# 20_ADC.net
KiCad netlist of a schematic drawn in Altium Designer
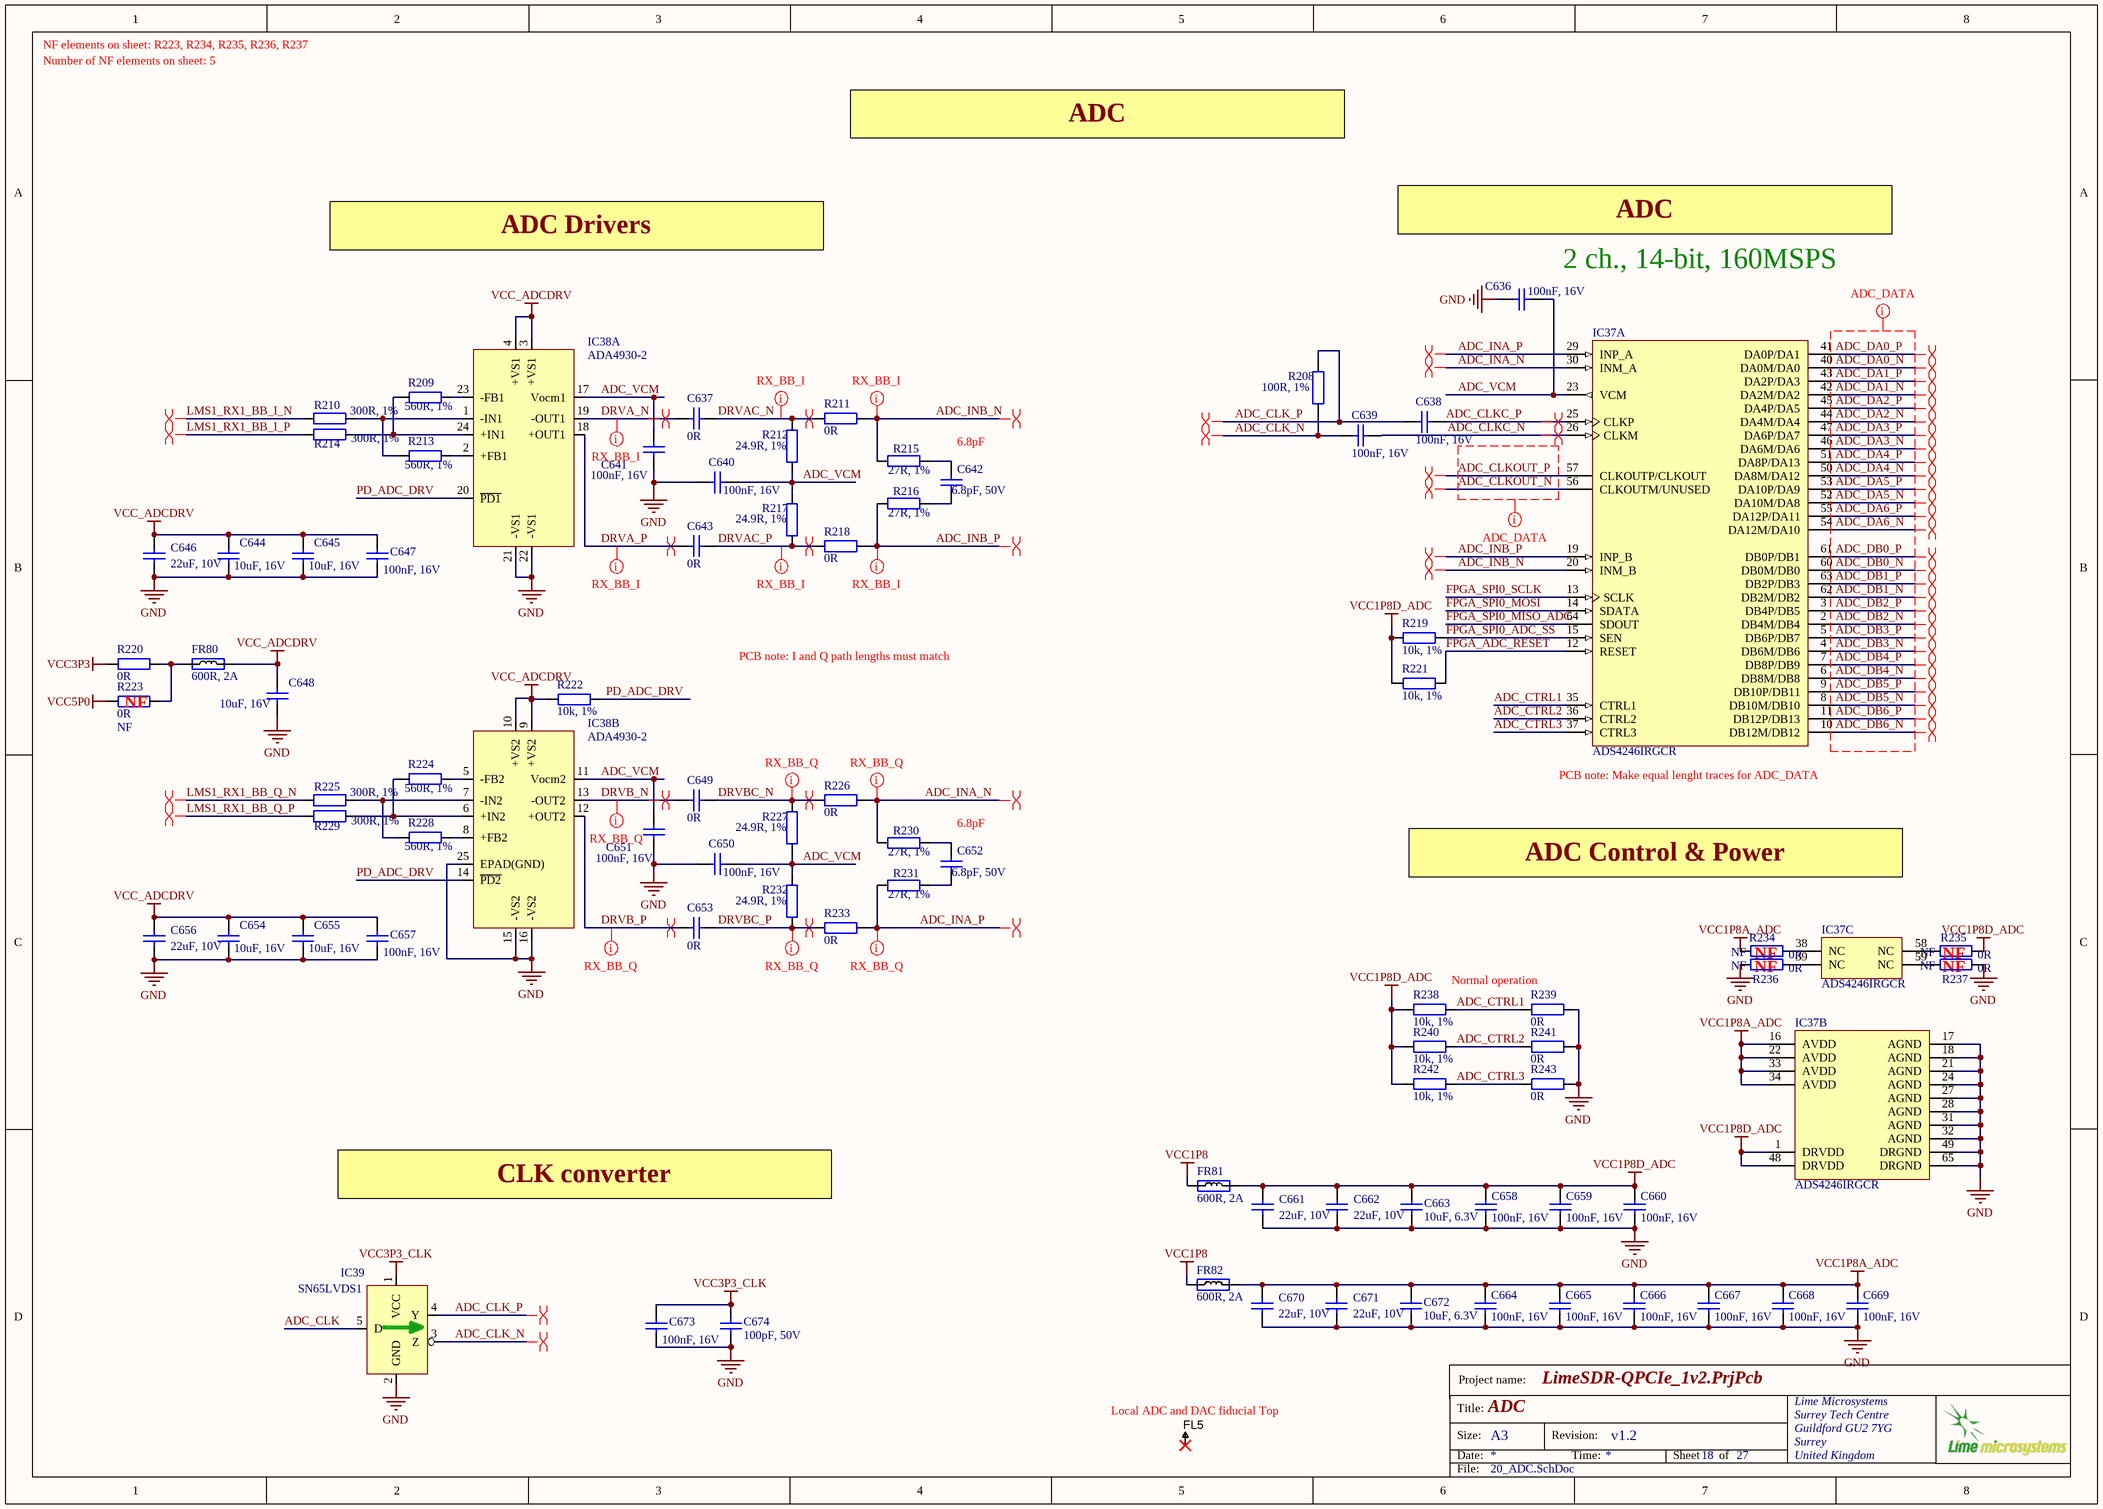
[diagram p0: 20_ADC.SchDoc]

(export (version "E")
  (design (tool "Eeschema 10.0.6"))
  (components
    (comp (ref "C636")
      (value "100nF, 16V")
      (footprint "CAP0402")
      (fields
        (field (name "TOLERANCE") "10 %")
        (field (name "MANUFACTURER") "Murata Electronics")
        (field (name "MANUFACTURER PART NUMBER") "GRM155R71C104KA88D")
      )
      (libsource (lib "LimeFPGAboard_schLib") (part "Cap_0603"))
    )
    (comp (ref "C637")
      (value "0R")
      (footprint "CAP0402")
      (fields (field (name "MANUFACTURER") "Yageo"))
      (libsource (lib "LimeFPGAboard_schLib") (part "Cap_0603"))
    )
    (comp (ref "C638")
      (value "100nF, 16V")
      (footprint "CAP0402")
      (fields
        (field (name "TOLERANCE") "10 %")
        (field (name "MANUFACTURER") "Murata Electronics")
        (field (name "MANUFACTURER PART NUMBER") "GRM155R71C104KA88D")
      )
      (libsource (lib "LimeFPGAboard_schLib") (part "Cap_0603"))
    )
    (comp (ref "C639")
      (value "100nF, 16V")
      (footprint "CAP0402")
      (fields
        (field (name "TOLERANCE") "10 %")
        (field (name "MANUFACTURER") "Murata Electronics")
        (field (name "MANUFACTURER PART NUMBER") "GRM155R71C104KA88D")
      )
      (libsource (lib "LimeFPGAboard_schLib") (part "Cap_0603"))
    )
    (comp (ref "C640")
      (value "100nF, 16V")
      (footprint "CAP0402")
      (fields
        (field (name "TOLERANCE") "10 %")
        (field (name "MANUFACTURER") "Murata Electronics")
        (field (name "MANUFACTURER PART NUMBER") "GRM155R71C104KA88D")
      )
      (libsource (lib "LimeFPGAboard_schLib") (part "Cap_0603"))
    )
    (comp (ref "C641")
      (value "100nF, 16V")
      (footprint "CAP0402")
      (fields
        (field (name "TOLERANCE") "10 %")
        (field (name "MANUFACTURER") "Murata Electronics")
        (field (name "MANUFACTURER PART NUMBER") "GRM155R71C104KA88D")
      )
      (libsource (lib "LimeFPGAboard_schLib") (part "Cap_0603"))
    )
    (comp (ref "C642")
      (value "6.8pF, 50V")
      (footprint "CAP0402")
      (fields
        (field (name "MANUFACTURER PART NUMBER") "GRM1555C1H6R8BA01D")
        (field (name "MANUFACTURER") "Murata Electronics North America")
        (field (name "TOLERANCE") "±0.1pF")
      )
      (libsource (lib "LimeFPGAboard_schLib") (part "Cap_0603"))
    )
    (comp (ref "C643")
      (value "0R")
      (footprint "CAP0402")
      (fields (field (name "MANUFACTURER") "Yageo"))
      (libsource (lib "LimeFPGAboard_schLib") (part "Cap_0603"))
    )
    (comp (ref "C644")
      (value "10uF, 16V")
      (footprint "CAP0603")
      (fields (field (name "MANUFACTURER") "Yageo") (field (name "TOLERANCE") "±20%"))
      (libsource (lib "LimeMicroAltiumLib_schLib") (part "Cap_0603"))
    )
    (comp (ref "C645")
      (value "10uF, 16V")
      (footprint "CAP0603")
      (fields (field (name "MANUFACTURER") "Yageo") (field (name "TOLERANCE") "±20%"))
      (libsource (lib "LimeMicroAltiumLib_schLib") (part "Cap_0603"))
    )
    (comp (ref "C646")
      (value "22uF, 10V")
      (footprint "CAP0603")
      (fields (field (name "TOLERANCE") "20 %") (field (name "MANUFACTURER") "TDK Corporation"))
      (libsource (lib "LimeFPGAboard_schLib") (part "Cap_0603"))
    )
    (comp (ref "C647")
      (value "100nF, 16V")
      (footprint "CAP0402")
      (fields
        (field (name "TOLERANCE") "10 %")
        (field (name "MANUFACTURER") "Murata Electronics")
        (field (name "MANUFACTURER PART NUMBER") "GRM155R71C104KA88D")
      )
      (libsource (lib "LimeFPGAboard_schLib") (part "Cap_0603"))
    )
    (comp (ref "C648")
      (value "10uF, 16V")
      (footprint "CAP0603")
      (fields (field (name "MANUFACTURER") "Yageo") (field (name "TOLERANCE") "±20%"))
      (libsource (lib "LimeMicroAltiumLib_schLib") (part "Cap_0603"))
    )
    (comp (ref "C649")
      (value "0R")
      (footprint "CAP0402")
      (fields (field (name "MANUFACTURER") "Yageo"))
      (libsource (lib "LimeFPGAboard_schLib") (part "Cap_0603"))
    )
    (comp (ref "C650")
      (value "100nF, 16V")
      (footprint "CAP0402")
      (fields
        (field (name "TOLERANCE") "10 %")
        (field (name "MANUFACTURER") "Murata Electronics")
        (field (name "MANUFACTURER PART NUMBER") "GRM155R71C104KA88D")
      )
      (libsource (lib "LimeFPGAboard_schLib") (part "Cap_0603"))
    )
    (comp (ref "C651")
      (value "100nF, 16V")
      (footprint "CAP0402")
      (fields
        (field (name "TOLERANCE") "10 %")
        (field (name "MANUFACTURER") "Murata Electronics")
        (field (name "MANUFACTURER PART NUMBER") "GRM155R71C104KA88D")
      )
      (libsource (lib "LimeFPGAboard_schLib") (part "Cap_0603"))
    )
    (comp (ref "C652")
      (value "6.8pF, 50V")
      (footprint "CAP0402")
      (fields
        (field (name "MANUFACTURER PART NUMBER") "GRM1555C1H6R8BA01D")
        (field (name "MANUFACTURER") "Murata Electronics North America")
        (field (name "TOLERANCE") "±0.1pF")
      )
      (libsource (lib "LimeFPGAboard_schLib") (part "Cap_0603"))
    )
    (comp (ref "C653")
      (value "0R")
      (footprint "CAP0402")
      (fields (field (name "MANUFACTURER") "Yageo"))
      (libsource (lib "LimeFPGAboard_schLib") (part "Cap_0603"))
    )
    (comp (ref "C654")
      (value "10uF, 16V")
      (footprint "CAP0603")
      (fields (field (name "MANUFACTURER") "Yageo") (field (name "TOLERANCE") "±20%"))
      (libsource (lib "LimeMicroAltiumLib_schLib") (part "Cap_0603"))
    )
    (comp (ref "C655")
      (value "10uF, 16V")
      (footprint "CAP0603")
      (fields (field (name "MANUFACTURER") "Yageo") (field (name "TOLERANCE") "±20%"))
      (libsource (lib "LimeMicroAltiumLib_schLib") (part "Cap_0603"))
    )
    (comp (ref "C656")
      (value "22uF, 10V")
      (footprint "CAP0603")
      (fields (field (name "TOLERANCE") "20 %") (field (name "MANUFACTURER") "TDK Corporation"))
      (libsource (lib "LimeFPGAboard_schLib") (part "Cap_0603"))
    )
    (comp (ref "C657")
      (value "100nF, 16V")
      (footprint "CAP0402")
      (fields
        (field (name "TOLERANCE") "10 %")
        (field (name "MANUFACTURER") "Murata Electronics")
        (field (name "MANUFACTURER PART NUMBER") "GRM155R71C104KA88D")
      )
      (libsource (lib "LimeFPGAboard_schLib") (part "Cap_0603"))
    )
    (comp (ref "C658")
      (value "100nF, 16V")
      (footprint "CAP0402")
      (fields
        (field (name "TOLERANCE") "10 %")
        (field (name "MANUFACTURER") "Murata Electronics")
        (field (name "MANUFACTURER PART NUMBER") "GRM155R71C104KA88D")
      )
      (libsource (lib "LimeFPGAboard_schLib") (part "Cap_0603"))
    )
    (comp (ref "C659")
      (value "100nF, 16V")
      (footprint "CAP0402")
      (fields
        (field (name "TOLERANCE") "10 %")
        (field (name "MANUFACTURER") "Murata Electronics")
        (field (name "MANUFACTURER PART NUMBER") "GRM155R71C104KA88D")
      )
      (libsource (lib "LimeFPGAboard_schLib") (part "Cap_0603"))
    )
    (comp (ref "C660")
      (value "100nF, 16V")
      (footprint "CAP0402")
      (fields
        (field (name "TOLERANCE") "10 %")
        (field (name "MANUFACTURER") "Murata Electronics")
        (field (name "MANUFACTURER PART NUMBER") "GRM155R71C104KA88D")
      )
      (libsource (lib "LimeFPGAboard_schLib") (part "Cap_0603"))
    )
    (comp (ref "C661")
      (value "22uF, 10V")
      (footprint "CAP0603")
      (fields (field (name "TOLERANCE") "20 %") (field (name "MANUFACTURER") "TDK Corporation"))
      (libsource (lib "LimeFPGAboard_schLib") (part "Cap_0603"))
    )
    (comp (ref "C662")
      (value "22uF, 10V")
      (footprint "CAP0603")
      (fields (field (name "TOLERANCE") "20 %") (field (name "MANUFACTURER") "TDK Corporation"))
      (libsource (lib "LimeFPGAboard_schLib") (part "Cap_0603"))
    )
    (comp (ref "C663")
      (value "10uF, 6.3V")
      (footprint "CAP0603")
      (fields (field (name "TOLERANCE") "±20%") (field (name "MANUFACTURER") "Yageo"))
      (libsource (lib "LimeFPGAboard_schLib") (part "Cap_0603"))
    )
    (comp (ref "C664")
      (value "100nF, 16V")
      (footprint "CAP0402")
      (fields
        (field (name "TOLERANCE") "10 %")
        (field (name "MANUFACTURER") "Murata Electronics")
        (field (name "MANUFACTURER PART NUMBER") "GRM155R71C104KA88D")
      )
      (libsource (lib "LimeFPGAboard_schLib") (part "Cap_0603"))
    )
    (comp (ref "C665")
      (value "100nF, 16V")
      (footprint "CAP0402")
      (fields
        (field (name "TOLERANCE") "10 %")
        (field (name "MANUFACTURER") "Murata Electronics")
        (field (name "MANUFACTURER PART NUMBER") "GRM155R71C104KA88D")
      )
      (libsource (lib "LimeFPGAboard_schLib") (part "Cap_0603"))
    )
    (comp (ref "C666")
      (value "100nF, 16V")
      (footprint "CAP0402")
      (fields
        (field (name "TOLERANCE") "10 %")
        (field (name "MANUFACTURER") "Murata Electronics")
        (field (name "MANUFACTURER PART NUMBER") "GRM155R71C104KA88D")
      )
      (libsource (lib "LimeFPGAboard_schLib") (part "Cap_0603"))
    )
    (comp (ref "C667")
      (value "100nF, 16V")
      (footprint "CAP0402")
      (fields
        (field (name "TOLERANCE") "10 %")
        (field (name "MANUFACTURER") "Murata Electronics")
        (field (name "MANUFACTURER PART NUMBER") "GRM155R71C104KA88D")
      )
      (libsource (lib "LimeFPGAboard_schLib") (part "Cap_0603"))
    )
    (comp (ref "C668")
      (value "100nF, 16V")
      (footprint "CAP0402")
      (fields
        (field (name "TOLERANCE") "10 %")
        (field (name "MANUFACTURER") "Murata Electronics")
        (field (name "MANUFACTURER PART NUMBER") "GRM155R71C104KA88D")
      )
      (libsource (lib "LimeFPGAboard_schLib") (part "Cap_0603"))
    )
    (comp (ref "C669")
      (value "100nF, 16V")
      (footprint "CAP0402")
      (fields
        (field (name "TOLERANCE") "10 %")
        (field (name "MANUFACTURER") "Murata Electronics")
        (field (name "MANUFACTURER PART NUMBER") "GRM155R71C104KA88D")
      )
      (libsource (lib "LimeFPGAboard_schLib") (part "Cap_0603"))
    )
    (comp (ref "C670")
      (value "22uF, 10V")
      (footprint "CAP0603")
      (fields (field (name "TOLERANCE") "20 %") (field (name "MANUFACTURER") "TDK Corporation"))
      (libsource (lib "LimeFPGAboard_schLib") (part "Cap_0603"))
    )
    (comp (ref "C671")
      (value "22uF, 10V")
      (footprint "CAP0603")
      (fields (field (name "TOLERANCE") "20 %") (field (name "MANUFACTURER") "TDK Corporation"))
      (libsource (lib "LimeFPGAboard_schLib") (part "Cap_0603"))
    )
    (comp (ref "C672")
      (value "10uF, 6.3V")
      (footprint "CAP0603")
      (fields (field (name "TOLERANCE") "±20%") (field (name "MANUFACTURER") "Yageo"))
      (libsource (lib "LimeFPGAboard_schLib") (part "Cap_0603"))
    )
    (comp (ref "C673")
      (value "100nF, 16V")
      (footprint "CAP0402")
      (fields
        (field (name "TOLERANCE") "10 %")
        (field (name "MANUFACTURER") "Murata Electronics")
        (field (name "MANUFACTURER PART NUMBER") "GRM155R71C104KA88D")
      )
      (libsource (lib "LimeFPGAboard_schLib") (part "Cap_0603"))
    )
    (comp (ref "C674")
      (value "100pF, 50V")
      (footprint "CAP0402")
      (fields (field (name "MANUFACTURER") "Yageo") (field (name "TOLERANCE") "±5%"))
      (libsource (lib "LimeMicroAltiumLib_schLib") (part "Cap_0402"))
    )
    (comp (ref "FL5")
      (value "Fiducial")
      (footprint "Fiducial_local")
      (libsource (lib "LimeMicroAltiumLib_schLib") (part "Fiducial"))
    )
    (comp (ref "FR80")
      (value "600R, 2A")
      (footprint "RES0805")
      (fields (field (name "MANUFACTURER") "TDK"))
      (libsource (lib "LimeMicroAltiumLib_schLib") (part "Ferrite"))
    )
    (comp (ref "FR81")
      (value "600R, 2A")
      (footprint "RES0805")
      (fields (field (name "MANUFACTURER") "TDK"))
      (libsource (lib "LimeFPGAboard_schLib") (part "Ferrite"))
    )
    (comp (ref "FR82")
      (value "600R, 2A")
      (footprint "RES0805")
      (fields (field (name "MANUFACTURER") "TDK"))
      (libsource (lib "LimeFPGAboard_schLib") (part "Ferrite"))
    )
    (comp (ref "IC37")
      (value "ADS4246IRGCR")
      (footprint "TI-RGC64-7400X7400TP_V")
      (description "14-Bit 160 MSPS Dual Low Power ADC, -40 to 85 degC, 64-pin QFN (RGC64), Green (RoHS & no Sb/Br)")
      (fields (field (name "MANUFACTURER") "Texas Instruments"))
      (libsource (lib "LimeMicroAltiumLib_schLib") (part "ADS4246IRGCR"))
    )
    (comp (ref "IC38")
      (value "ADA4930-2")
      (footprint "ADA4930-2_LFCSP-24")
      (fields (field (name "MANUFACTURER") "Analog Devices Inc."))
      (libsource (lib "LimeMicroAltiumLib_schLib") (part "ADA4930-2"))
    )
    (comp (ref "IC39")
      (value "SN65LVDS1")
      (footprint "SOT23-5")
      (fields (field (name "MANUFACTURER") "TEXAS INSTRUMENTS"))
      (libsource (lib "LimeMicroAltiumLib_schLib") (part "SN65LVDS1"))
    )
    (comp (ref "R208")
      (value "100R, 1%")
      (footprint "RES0402")
      (fields (field (name "TOLERANCE") "±1%") (field (name "MANUFACTURER") "Stackpole Electronics Inc."))
      (libsource (lib "LimeFPGAboard_schLib") (part "Res_0402"))
    )
    (comp (ref "R209")
      (value "560R, 1%")
      (footprint "RES0402")
      (fields (field (name "TOLERANCE") "±1%") (field (name "MANUFACTURER") "Vishay Dale"))
      (libsource (lib "LimeFPGAboard_schLib") (part "Res_0402"))
    )
    (comp (ref "R210")
      (value "300R, 1%")
      (footprint "RES0402")
      (fields (field (name "TOLERANCE") "±1%") (field (name "MANUFACTURER") "Vishay Dale"))
      (libsource (lib "LimeFPGAboard_schLib") (part "Res_0402"))
    )
    (comp (ref "R211")
      (value "0R")
      (footprint "RES0402")
      (fields (field (name "MANUFACTURER") "Yageo"))
      (libsource (lib "LimeFPGAboard_schLib") (part "Res_0402"))
    )
    (comp (ref "R212")
      (value "24.9R, 1%")
      (footprint "RES0402")
      (fields (field (name "TOLERANCE") "±1%") (field (name "MANUFACTURER") "Vishay Dale"))
      (libsource (lib "LimeFPGAboard_schLib") (part "Res_0402"))
    )
    (comp (ref "R213")
      (value "560R, 1%")
      (footprint "RES0402")
      (fields (field (name "TOLERANCE") "±1%") (field (name "MANUFACTURER") "Vishay Dale"))
      (libsource (lib "LimeFPGAboard_schLib") (part "Res_0402"))
    )
    (comp (ref "R214")
      (value "300R, 1%")
      (footprint "RES0402")
      (fields (field (name "TOLERANCE") "±1%") (field (name "MANUFACTURER") "Vishay Dale"))
      (libsource (lib "LimeFPGAboard_schLib") (part "Res_0402"))
    )
    (comp (ref "R215")
      (value "27R, 1%")
      (footprint "RES0402")
      (fields (field (name "TOLERANCE") "±1%") (field (name "MANUFACTURER") "Vishay Dale"))
      (libsource (lib "LimeFPGAboard_schLib") (part "Res_0402"))
    )
    (comp (ref "R216")
      (value "27R, 1%")
      (footprint "RES0402")
      (fields (field (name "TOLERANCE") "±1%") (field (name "MANUFACTURER") "Vishay Dale"))
      (libsource (lib "LimeFPGAboard_schLib") (part "Res_0402"))
    )
    (comp (ref "R217")
      (value "24.9R, 1%")
      (footprint "RES0402")
      (fields (field (name "TOLERANCE") "±1%") (field (name "MANUFACTURER") "Vishay Dale"))
      (libsource (lib "LimeFPGAboard_schLib") (part "Res_0402"))
    )
    (comp (ref "R218")
      (value "0R")
      (footprint "RES0402")
      (fields (field (name "MANUFACTURER") "Yageo"))
      (libsource (lib "LimeFPGAboard_schLib") (part "Res_0402"))
    )
    (comp (ref "R219")
      (value "10k, 1%")
      (footprint "RES0402")
      (fields (field (name "MANUFACTURER") "Yageo") (field (name "TOLERANCE") "±1%"))
      (libsource (lib "LimeMicroAltiumLib_schLib") (part "Res_0402"))
    )
    (comp (ref "R220")
      (value "0R")
      (footprint "RES0402")
      (fields (field (name "MANUFACTURER") "Yageo") (field (name "TOLERANCE") "Jumper"))
      (libsource (lib "LimeMicroAltiumLib_schLib") (part "Res_0402"))
    )
    (comp (ref "R221")
      (value "10k, 1%")
      (footprint "RES0402")
      (fields (field (name "MANUFACTURER") "Yageo") (field (name "TOLERANCE") "±1%"))
      (libsource (lib "LimeMicroAltiumLib_schLib") (part "Res_0402"))
    )
    (comp (ref "R222")
      (value "10k, 1%")
      (footprint "RES0402")
      (fields (field (name "MANUFACTURER") "Yageo") (field (name "TOLERANCE") "±1%"))
      (libsource (lib "LimeMicroAltiumLib_schLib") (part "Res_0402"))
    )
    (comp (ref "R223")
      (value "0R")
      (footprint "RES0402")
      (fields
        (field (name "ASSEMBLY INFO") "NF")
        (field (name "MANUFACTURER") "Yageo")
        (field (name "TOLERANCE") "Jumper")
      )
      (libsource (lib "LimeMicroAltiumLib_schLib") (part "Res_0402"))
    )
    (comp (ref "R224")
      (value "560R, 1%")
      (footprint "RES0402")
      (fields (field (name "TOLERANCE") "±1%") (field (name "MANUFACTURER") "Vishay Dale"))
      (libsource (lib "LimeFPGAboard_schLib") (part "Res_0402"))
    )
    (comp (ref "R225")
      (value "300R, 1%")
      (footprint "RES0402")
      (fields (field (name "TOLERANCE") "±1%") (field (name "MANUFACTURER") "Vishay Dale"))
      (libsource (lib "LimeFPGAboard_schLib") (part "Res_0402"))
    )
    (comp (ref "R226")
      (value "0R")
      (footprint "RES0402")
      (fields (field (name "MANUFACTURER") "Yageo"))
      (libsource (lib "LimeFPGAboard_schLib") (part "Res_0402"))
    )
    (comp (ref "R227")
      (value "24.9R, 1%")
      (footprint "RES0402")
      (fields (field (name "TOLERANCE") "±1%") (field (name "MANUFACTURER") "Vishay Dale"))
      (libsource (lib "LimeFPGAboard_schLib") (part "Res_0402"))
    )
    (comp (ref "R228")
      (value "560R, 1%")
      (footprint "RES0402")
      (fields (field (name "TOLERANCE") "±1%") (field (name "MANUFACTURER") "Vishay Dale"))
      (libsource (lib "LimeFPGAboard_schLib") (part "Res_0402"))
    )
    (comp (ref "R229")
      (value "300R, 1%")
      (footprint "RES0402")
      (fields (field (name "TOLERANCE") "±1%") (field (name "MANUFACTURER") "Vishay Dale"))
      (libsource (lib "LimeFPGAboard_schLib") (part "Res_0402"))
    )
    (comp (ref "R230")
      (value "27R, 1%")
      (footprint "RES0402")
      (fields (field (name "TOLERANCE") "±1%") (field (name "MANUFACTURER") "Vishay Dale"))
      (libsource (lib "LimeFPGAboard_schLib") (part "Res_0402"))
    )
    (comp (ref "R231")
      (value "27R, 1%")
      (footprint "RES0402")
      (fields (field (name "TOLERANCE") "±1%") (field (name "MANUFACTURER") "Vishay Dale"))
      (libsource (lib "LimeFPGAboard_schLib") (part "Res_0402"))
    )
    (comp (ref "R232")
      (value "24.9R, 1%")
      (footprint "RES0402")
      (fields (field (name "TOLERANCE") "±1%") (field (name "MANUFACTURER") "Vishay Dale"))
      (libsource (lib "LimeFPGAboard_schLib") (part "Res_0402"))
    )
    (comp (ref "R233")
      (value "0R")
      (footprint "RES0402")
      (fields (field (name "MANUFACTURER") "Yageo"))
      (libsource (lib "LimeFPGAboard_schLib") (part "Res_0402"))
    )
    (comp (ref "R234")
      (value "0R")
      (footprint "RES0402")
      (fields (field (name "MANUFACTURER") "Yageo") (field (name "ASSEMBLY INFO") "NF"))
      (libsource (lib "LimeFPGAboard_schLib") (part "Res_0402"))
    )
    (comp (ref "R235")
      (value "0R")
      (footprint "RES0402")
      (fields (field (name "MANUFACTURER") "Yageo") (field (name "ASSEMBLY INFO") "NF"))
      (libsource (lib "LimeFPGAboard_schLib") (part "Res_0402"))
    )
    (comp (ref "R236")
      (value "0R")
      (footprint "RES0402")
      (fields (field (name "MANUFACTURER") "Yageo") (field (name "ASSEMBLY INFO") "NF"))
      (libsource (lib "LimeFPGAboard_schLib") (part "Res_0402"))
    )
    (comp (ref "R237")
      (value "0R")
      (footprint "RES0402")
      (fields (field (name "MANUFACTURER") "Yageo") (field (name "ASSEMBLY INFO") "NF"))
      (libsource (lib "LimeFPGAboard_schLib") (part "Res_0402"))
    )
    (comp (ref "R238")
      (value "10k, 1%")
      (footprint "RES0402")
      (fields (field (name "MANUFACTURER") "Yageo") (field (name "TOLERANCE") "±1%"))
      (libsource (lib "LimeMicroAltiumLib_schLib") (part "Res_0402"))
    )
    (comp (ref "R239")
      (value "0R")
      (footprint "RES0402")
      (fields (field (name "MANUFACTURER") "Yageo"))
      (libsource (lib "LimeFPGAboard_schLib") (part "Res_0402"))
    )
    (comp (ref "R240")
      (value "10k, 1%")
      (footprint "RES0402")
      (fields (field (name "MANUFACTURER") "Yageo") (field (name "TOLERANCE") "±1%"))
      (libsource (lib "LimeMicroAltiumLib_schLib") (part "Res_0402"))
    )
    (comp (ref "R241")
      (value "0R")
      (footprint "RES0402")
      (fields (field (name "MANUFACTURER") "Yageo"))
      (libsource (lib "LimeFPGAboard_schLib") (part "Res_0402"))
    )
    (comp (ref "R242")
      (value "10k, 1%")
      (footprint "RES0402")
      (fields (field (name "MANUFACTURER") "Yageo") (field (name "TOLERANCE") "±1%"))
      (libsource (lib "LimeMicroAltiumLib_schLib") (part "Res_0402"))
    )
    (comp (ref "R243")
      (value "0R")
      (footprint "RES0402")
      (fields (field (name "MANUFACTURER") "Yageo"))
      (libsource (lib "LimeFPGAboard_schLib") (part "Res_0402"))
    )
  )
  (nets
    (net (code "1") (name "/ADC_CLK") (class "Default")
      (node (ref "IC39") (pin "5") (pinfunction "D_5") (pintype "passive"))
    )
    (net (code "2") (name "/ADC_CLKC_N") (class "Default")
      (node (ref "C639") (pin "1") (pinfunction "1_1") (pintype "passive"))
      (node (ref "IC37") (pin "26") (pinfunction "CLKM_26") (pintype "input"))
    )
    (net (code "3") (name "/ADC_CLKC_P") (class "Default")
      (node (ref "C638") (pin "1") (pinfunction "1_1") (pintype "passive"))
      (node (ref "IC37") (pin "25") (pinfunction "CLKP_25") (pintype "input"))
    )
    (net (code "4") (name "/ADC_CLKOUT_N") (class "Default")
      (node (ref "IC37") (pin "56") (pinfunction "CLKOUTM/UNUSED_56") (pintype "tri_state"))
    )
    (net (code "5") (name "/ADC_CLKOUT_P") (class "Default")
      (node (ref "IC37") (pin "57") (pinfunction "CLKOUTP/CLKOUT_57") (pintype "tri_state"))
    )
    (net (code "6") (name "/ADC_CLK_N") (class "Default")
      (node (ref "C639") (pin "2") (pinfunction "2_2") (pintype "passive"))
      (node (ref "IC39") (pin "3") (pinfunction "Z_3") (pintype "passive"))
      (node (ref "R208") (pin "1") (pinfunction "1_1") (pintype "passive"))
    )
    (net (code "7") (name "/ADC_CLK_P") (class "Default")
      (node (ref "C638") (pin "2") (pinfunction "2_2") (pintype "passive"))
      (node (ref "IC39") (pin "4") (pinfunction "Y_4") (pintype "passive"))
      (node (ref "R208") (pin "2") (pinfunction "2_2") (pintype "passive"))
    )
    (net (code "8") (name "/ADC_CTRL1") (class "Default")
      (node (ref "IC37") (pin "35") (pinfunction "CTRL1_35") (pintype "input"))
      (node (ref "R238") (pin "1") (pinfunction "1_1") (pintype "passive"))
      (node (ref "R239") (pin "2") (pinfunction "2_2") (pintype "passive"))
    )
    (net (code "9") (name "/ADC_CTRL2") (class "Default")
      (node (ref "IC37") (pin "36") (pinfunction "CTRL2_36") (pintype "input"))
      (node (ref "R240") (pin "1") (pinfunction "1_1") (pintype "passive"))
      (node (ref "R241") (pin "2") (pinfunction "2_2") (pintype "passive"))
    )
    (net (code "10") (name "/ADC_CTRL3") (class "Default")
      (node (ref "IC37") (pin "37") (pinfunction "CTRL3_37") (pintype "input"))
      (node (ref "R242") (pin "1") (pinfunction "1_1") (pintype "passive"))
      (node (ref "R243") (pin "2") (pinfunction "2_2") (pintype "passive"))
    )
    (net (code "11") (name "/ADC_DA0_N") (class "Default")
      (node (ref "IC37") (pin "40") (pinfunction "DA0M/DA0_40") (pintype "tri_state"))
    )
    (net (code "12") (name "/ADC_DA0_P") (class "Default")
      (node (ref "IC37") (pin "41") (pinfunction "DA0P/DA1_41") (pintype "tri_state"))
    )
    (net (code "13") (name "/ADC_DA1_N") (class "Default")
      (node (ref "IC37") (pin "42") (pinfunction "DA2M/DA2_42") (pintype "tri_state"))
    )
    (net (code "14") (name "/ADC_DA1_P") (class "Default")
      (node (ref "IC37") (pin "43") (pinfunction "DA2P/DA3_43") (pintype "tri_state"))
    )
    (net (code "15") (name "/ADC_DA2_N") (class "Default")
      (node (ref "IC37") (pin "44") (pinfunction "DA4M/DA4_44") (pintype "tri_state"))
    )
    (net (code "16") (name "/ADC_DA2_P") (class "Default")
      (node (ref "IC37") (pin "45") (pinfunction "DA4P/DA5_45") (pintype "tri_state"))
    )
    (net (code "17") (name "/ADC_DA3_N") (class "Default")
      (node (ref "IC37") (pin "46") (pinfunction "DA6M/DA6_46") (pintype "tri_state"))
    )
    (net (code "18") (name "/ADC_DA3_P") (class "Default")
      (node (ref "IC37") (pin "47") (pinfunction "DA6P/DA7_47") (pintype "tri_state"))
    )
    (net (code "19") (name "/ADC_DA4_N") (class "Default")
      (node (ref "IC37") (pin "50") (pinfunction "DA8M/DA12_50") (pintype "tri_state"))
    )
    (net (code "20") (name "/ADC_DA4_P") (class "Default")
      (node (ref "IC37") (pin "51") (pinfunction "DA8P/DA13_51") (pintype "tri_state"))
    )
    (net (code "21") (name "/ADC_DA5_N") (class "Default")
      (node (ref "IC37") (pin "52") (pinfunction "DA10M/DA8_52") (pintype "tri_state"))
    )
    (net (code "22") (name "/ADC_DA5_P") (class "Default")
      (node (ref "IC37") (pin "53") (pinfunction "DA10P/DA9_53") (pintype "tri_state"))
    )
    (net (code "23") (name "/ADC_DA6_N") (class "Default")
      (node (ref "IC37") (pin "54") (pinfunction "DA12M/DA10_54") (pintype "tri_state"))
    )
    (net (code "24") (name "/ADC_DA6_P") (class "Default")
      (node (ref "IC37") (pin "55") (pinfunction "DA12P/DA11_55") (pintype "tri_state"))
    )
    (net (code "25") (name "/ADC_DB0_N") (class "Default")
      (node (ref "IC37") (pin "60") (pinfunction "DB0M/DB0_60") (pintype "tri_state"))
    )
    (net (code "26") (name "/ADC_DB0_P") (class "Default")
      (node (ref "IC37") (pin "61") (pinfunction "DB0P/DB1_61") (pintype "tri_state"))
    )
    (net (code "27") (name "/ADC_DB1_N") (class "Default")
      (node (ref "IC37") (pin "62") (pinfunction "DB2M/DB2_62") (pintype "tri_state"))
    )
    (net (code "28") (name "/ADC_DB1_P") (class "Default")
      (node (ref "IC37") (pin "63") (pinfunction "DB2P/DB3_63") (pintype "tri_state"))
    )
    (net (code "29") (name "/ADC_DB2_N") (class "Default")
      (node (ref "IC37") (pin "2") (pinfunction "DB4M/DB4_2") (pintype "tri_state"))
    )
    (net (code "30") (name "/ADC_DB2_P") (class "Default")
      (node (ref "IC37") (pin "3") (pinfunction "DB4P/DB5_3") (pintype "tri_state"))
    )
    (net (code "31") (name "/ADC_DB3_N") (class "Default")
      (node (ref "IC37") (pin "4") (pinfunction "DB6M/DB6_4") (pintype "tri_state"))
    )
    (net (code "32") (name "/ADC_DB3_P") (class "Default")
      (node (ref "IC37") (pin "5") (pinfunction "DB6P/DB7_5") (pintype "tri_state"))
    )
    (net (code "33") (name "/ADC_DB4_N") (class "Default")
      (node (ref "IC37") (pin "6") (pinfunction "DB8M/DB8_6") (pintype "tri_state"))
    )
    (net (code "34") (name "/ADC_DB4_P") (class "Default")
      (node (ref "IC37") (pin "7") (pinfunction "DB8P/DB9_7") (pintype "tri_state"))
    )
    (net (code "35") (name "/ADC_DB5_N") (class "Default")
      (node (ref "IC37") (pin "8") (pinfunction "DB10M/DB10_8") (pintype "tri_state"))
    )
    (net (code "36") (name "/ADC_DB5_P") (class "Default")
      (node (ref "IC37") (pin "9") (pinfunction "DB10P/DB11_9") (pintype "tri_state"))
    )
    (net (code "37") (name "/ADC_DB6_N") (class "Default")
      (node (ref "IC37") (pin "10") (pinfunction "DB12M/DB12_10") (pintype "tri_state"))
    )
    (net (code "38") (name "/ADC_DB6_P") (class "Default")
      (node (ref "IC37") (pin "11") (pinfunction "DB12P/DB13_11") (pintype "tri_state"))
    )
    (net (code "39") (name "/ADC_INA_N") (class "Default")
      (node (ref "IC37") (pin "30") (pinfunction "INM_A_30") (pintype "input"))
      (node (ref "R226") (pin "1") (pinfunction "1_1") (pintype "passive"))
      (node (ref "R230") (pin "1") (pinfunction "1_1") (pintype "passive"))
    )
    (net (code "40") (name "/ADC_INA_P") (class "Default")
      (node (ref "IC37") (pin "29") (pinfunction "INP_A_29") (pintype "input"))
      (node (ref "R231") (pin "1") (pinfunction "1_1") (pintype "passive"))
      (node (ref "R233") (pin "1") (pinfunction "1_1") (pintype "passive"))
    )
    (net (code "41") (name "/ADC_INB_N") (class "Default")
      (node (ref "IC37") (pin "20") (pinfunction "INM_B_20") (pintype "input"))
      (node (ref "R211") (pin "1") (pinfunction "1_1") (pintype "passive"))
      (node (ref "R215") (pin "1") (pinfunction "1_1") (pintype "passive"))
    )
    (net (code "42") (name "/ADC_INB_P") (class "Default")
      (node (ref "IC37") (pin "19") (pinfunction "INP_B_19") (pintype "input"))
      (node (ref "R216") (pin "1") (pinfunction "1_1") (pintype "passive"))
      (node (ref "R218") (pin "1") (pinfunction "1_1") (pintype "passive"))
    )
    (net (code "43") (name "/ADC_VCM") (class "Default")
      (node (ref "C636") (pin "2") (pinfunction "2_2") (pintype "passive"))
      (node (ref "C640") (pin "1") (pinfunction "1_1") (pintype "passive"))
      (node (ref "C641") (pin "1") (pinfunction "1_1") (pintype "passive"))
      (node (ref "C650") (pin "1") (pinfunction "1_1") (pintype "passive"))
      (node (ref "C651") (pin "1") (pinfunction "1_1") (pintype "passive"))
      (node (ref "IC37") (pin "23") (pinfunction "VCM_23") (pintype "output"))
      (node (ref "IC38") (pin "11") (pinfunction "Vocm2_11") (pintype "input"))
      (node (ref "IC38") (pin "17") (pinfunction "Vocm1_17") (pintype "input"))
      (node (ref "R212") (pin "1") (pinfunction "1_1") (pintype "passive"))
      (node (ref "R217") (pin "2") (pinfunction "2_2") (pintype "passive"))
      (node (ref "R227") (pin "1") (pinfunction "1_1") (pintype "passive"))
      (node (ref "R232") (pin "2") (pinfunction "2_2") (pintype "passive"))
    )
    (net (code "44") (name "/DRVAC_N") (class "Default")
      (node (ref "C637") (pin "1") (pinfunction "1_1") (pintype "passive"))
      (node (ref "R211") (pin "2") (pinfunction "2_2") (pintype "passive"))
      (node (ref "R212") (pin "2") (pinfunction "2_2") (pintype "passive"))
    )
    (net (code "45") (name "/DRVAC_P") (class "Default")
      (node (ref "C643") (pin "1") (pinfunction "1_1") (pintype "passive"))
      (node (ref "R217") (pin "1") (pinfunction "1_1") (pintype "passive"))
      (node (ref "R218") (pin "2") (pinfunction "2_2") (pintype "passive"))
    )
    (net (code "46") (name "/DRVA_N") (class "Default")
      (node (ref "C637") (pin "2") (pinfunction "2_2") (pintype "passive"))
      (node (ref "IC38") (pin "19") (pinfunction "-OUT1_19") (pintype "output"))
    )
    (net (code "47") (name "/DRVA_P") (class "Default")
      (node (ref "C643") (pin "2") (pinfunction "2_2") (pintype "passive"))
      (node (ref "IC38") (pin "18") (pinfunction "+OUT1_18") (pintype "output"))
    )
    (net (code "48") (name "/DRVBC_N") (class "Default")
      (node (ref "C649") (pin "1") (pinfunction "1_1") (pintype "passive"))
      (node (ref "R226") (pin "2") (pinfunction "2_2") (pintype "passive"))
      (node (ref "R227") (pin "2") (pinfunction "2_2") (pintype "passive"))
    )
    (net (code "49") (name "/DRVBC_P") (class "Default")
      (node (ref "C653") (pin "1") (pinfunction "1_1") (pintype "passive"))
      (node (ref "R232") (pin "1") (pinfunction "1_1") (pintype "passive"))
      (node (ref "R233") (pin "2") (pinfunction "2_2") (pintype "passive"))
    )
    (net (code "50") (name "/DRVB_N") (class "Default")
      (node (ref "C649") (pin "2") (pinfunction "2_2") (pintype "passive"))
      (node (ref "IC38") (pin "13") (pinfunction "-OUT2_13") (pintype "output"))
    )
    (net (code "51") (name "/DRVB_P") (class "Default")
      (node (ref "C653") (pin "2") (pinfunction "2_2") (pintype "passive"))
      (node (ref "IC38") (pin "12") (pinfunction "+OUT2_12") (pintype "output"))
    )
    (net (code "52") (name "/FPGA_ADC_RESET") (class "Default")
      (node (ref "IC37") (pin "12") (pinfunction "RESET_12") (pintype "input"))
      (node (ref "R221") (pin "1") (pinfunction "1_1") (pintype "passive"))
    )
    (net (code "53") (name "/FPGA_SPI0_ADC_SS") (class "Default")
      (node (ref "IC37") (pin "15") (pinfunction "SEN_15") (pintype "input"))
      (node (ref "R219") (pin "1") (pinfunction "1_1") (pintype "passive"))
    )
    (net (code "54") (name "/FPGA_SPI0_MISO_ADC") (class "Default")
      (node (ref "IC37") (pin "64") (pinfunction "SDOUT_64") (pintype "tri_state"))
    )
    (net (code "55") (name "/FPGA_SPI0_MOSI") (class "Default")
      (node (ref "IC37") (pin "14") (pinfunction "SDATA_14") (pintype "input"))
    )
    (net (code "56") (name "/FPGA_SPI0_SCLK") (class "Default")
      (node (ref "IC37") (pin "13") (pinfunction "SCLK_13") (pintype "input"))
    )
    (net (code "57") (name "/LMS1_RX1_BB_I_N") (class "Default")
      (node (ref "R210") (pin "2") (pinfunction "2_2") (pintype "passive"))
    )
    (net (code "58") (name "/LMS1_RX1_BB_I_P") (class "Default")
      (node (ref "R214") (pin "2") (pinfunction "2_2") (pintype "passive"))
    )
    (net (code "59") (name "/LMS1_RX1_BB_Q_N") (class "Default")
      (node (ref "R225") (pin "2") (pinfunction "2_2") (pintype "passive"))
    )
    (net (code "60") (name "/LMS1_RX1_BB_Q_P") (class "Default")
      (node (ref "R229") (pin "2") (pinfunction "2_2") (pintype "passive"))
    )
    (net (code "61") (name "/PD_ADC_DRV") (class "Default")
      (node (ref "IC38") (pin "14") (pinfunction "~{PD2}_14") (pintype "input"))
      (node (ref "IC38") (pin "20") (pinfunction "~{PD1}_20") (pintype "input"))
      (node (ref "R222") (pin "1") (pinfunction "1_1") (pintype "passive"))
    )
    (net (code "62") (name "GND") (class "Default")
      (node (ref "C636") (pin "1") (pinfunction "1_1") (pintype "passive"))
      (node (ref "C640") (pin "2") (pinfunction "2_2") (pintype "passive"))
      (node (ref "C641") (pin "2") (pinfunction "2_2") (pintype "passive"))
      (node (ref "C644") (pin "1") (pinfunction "1_1") (pintype "passive"))
      (node (ref "C645") (pin "1") (pinfunction "1_1") (pintype "passive"))
      (node (ref "C646") (pin "1") (pinfunction "1_1") (pintype "passive"))
      (node (ref "C647") (pin "2") (pinfunction "2_2") (pintype "passive"))
      (node (ref "C648") (pin "1") (pinfunction "1_1") (pintype "passive"))
      (node (ref "C650") (pin "2") (pinfunction "2_2") (pintype "passive"))
      (node (ref "C651") (pin "2") (pinfunction "2_2") (pintype "passive"))
      (node (ref "C654") (pin "1") (pinfunction "1_1") (pintype "passive"))
      (node (ref "C655") (pin "1") (pinfunction "1_1") (pintype "passive"))
      (node (ref "C656") (pin "1") (pinfunction "1_1") (pintype "passive"))
      (node (ref "C657") (pin "2") (pinfunction "2_2") (pintype "passive"))
      (node (ref "C658") (pin "1") (pinfunction "1_1") (pintype "passive"))
      (node (ref "C659") (pin "1") (pinfunction "1_1") (pintype "passive"))
      (node (ref "C660") (pin "1") (pinfunction "1_1") (pintype "passive"))
      (node (ref "C661") (pin "1") (pinfunction "1_1") (pintype "passive"))
      (node (ref "C662") (pin "1") (pinfunction "1_1") (pintype "passive"))
      (node (ref "C663") (pin "2") (pinfunction "2_2") (pintype "passive"))
      (node (ref "C664") (pin "1") (pinfunction "1_1") (pintype "passive"))
      (node (ref "C665") (pin "1") (pinfunction "1_1") (pintype "passive"))
      (node (ref "C666") (pin "1") (pinfunction "1_1") (pintype "passive"))
      (node (ref "C667") (pin "1") (pinfunction "1_1") (pintype "passive"))
      (node (ref "C668") (pin "1") (pinfunction "1_1") (pintype "passive"))
      (node (ref "C669") (pin "1") (pinfunction "1_1") (pintype "passive"))
      (node (ref "C670") (pin "1") (pinfunction "1_1") (pintype "passive"))
      (node (ref "C671") (pin "1") (pinfunction "1_1") (pintype "passive"))
      (node (ref "C672") (pin "2") (pinfunction "2_2") (pintype "passive"))
      (node (ref "C673") (pin "2") (pinfunction "2_2") (pintype "passive"))
      (node (ref "C674") (pin "1") (pinfunction "1_1") (pintype "passive"))
      (node (ref "IC37") (pin "17") (pinfunction "AGND_17") (pintype "power_in"))
      (node (ref "IC37") (pin "18") (pinfunction "AGND_18") (pintype "power_in"))
      (node (ref "IC37") (pin "21") (pinfunction "AGND_21") (pintype "power_in"))
      (node (ref "IC37") (pin "24") (pinfunction "AGND_24") (pintype "power_in"))
      (node (ref "IC37") (pin "27") (pinfunction "AGND_27") (pintype "power_in"))
      (node (ref "IC37") (pin "28") (pinfunction "AGND_28") (pintype "power_in"))
      (node (ref "IC37") (pin "31") (pinfunction "AGND_31") (pintype "power_in"))
      (node (ref "IC37") (pin "32") (pinfunction "AGND_32") (pintype "power_in"))
      (node (ref "IC37") (pin "49") (pinfunction "DRGND_49") (pintype "power_in"))
      (node (ref "IC37") (pin "65") (pinfunction "DRGND_65") (pintype "power_in"))
      (node (ref "IC38") (pin "15") (pinfunction "-VS2_15") (pintype "power_in"))
      (node (ref "IC38") (pin "16") (pinfunction "-VS2_16") (pintype "power_in"))
      (node (ref "IC38") (pin "21") (pinfunction "-VS1_21") (pintype "power_in"))
      (node (ref "IC38") (pin "22") (pinfunction "-VS1_22") (pintype "power_in"))
      (node (ref "IC38") (pin "25") (pinfunction "EPAD(GND)_25") (pintype "passive"))
      (node (ref "IC39") (pin "2") (pinfunction "GND_2") (pintype "passive"))
      (node (ref "R236") (pin "1") (pinfunction "1_1") (pintype "passive"))
      (node (ref "R237") (pin "2") (pinfunction "2_2") (pintype "passive"))
      (node (ref "R239") (pin "1") (pinfunction "1_1") (pintype "passive"))
      (node (ref "R241") (pin "1") (pinfunction "1_1") (pintype "passive"))
      (node (ref "R243") (pin "1") (pinfunction "1_1") (pintype "passive"))
    )
    (net (code "63") (name "Net-(C642-Pad1)") (class "Default")
      (node (ref "C642") (pin "1") (pinfunction "1_1") (pintype "passive"))
      (node (ref "R215") (pin "2") (pinfunction "2_2") (pintype "passive"))
    )
    (net (code "64") (name "Net-(C642-Pad2)") (class "Default")
      (node (ref "C642") (pin "2") (pinfunction "2_2") (pintype "passive"))
      (node (ref "R216") (pin "2") (pinfunction "2_2") (pintype "passive"))
    )
    (net (code "65") (name "Net-(C652-Pad1)") (class "Default")
      (node (ref "C652") (pin "1") (pinfunction "1_1") (pintype "passive"))
      (node (ref "R230") (pin "2") (pinfunction "2_2") (pintype "passive"))
    )
    (net (code "66") (name "Net-(C652-Pad2)") (class "Default")
      (node (ref "C652") (pin "2") (pinfunction "2_2") (pintype "passive"))
      (node (ref "R231") (pin "2") (pinfunction "2_2") (pintype "passive"))
    )
    (net (code "67") (name "Net-(FR80-Pad1)") (class "Default")
      (node (ref "FR80") (pin "1") (pinfunction "1_1") (pintype "passive"))
      (node (ref "R220") (pin "1") (pinfunction "1_1") (pintype "passive"))
      (node (ref "R223") (pin "1") (pinfunction "1_1") (pintype "passive"))
    )
    (net (code "68") (name "Net-(IC37C-NC-Pad38)") (class "Default")
      (node (ref "IC37") (pin "38") (pinfunction "NC_38") (pintype "passive"))
      (node (ref "R234") (pin "2") (pinfunction "2_2") (pintype "passive"))
    )
    (net (code "69") (name "Net-(IC37C-NC-Pad39)") (class "Default")
      (node (ref "IC37") (pin "39") (pinfunction "NC_39") (pintype "passive"))
      (node (ref "R236") (pin "2") (pinfunction "2_2") (pintype "passive"))
    )
    (net (code "70") (name "Net-(IC37C-NC-Pad58)") (class "Default")
      (node (ref "IC37") (pin "58") (pinfunction "NC_58") (pintype "passive"))
      (node (ref "R235") (pin "1") (pinfunction "1_1") (pintype "passive"))
    )
    (net (code "71") (name "Net-(IC37C-NC-Pad59)") (class "Default")
      (node (ref "IC37") (pin "59") (pinfunction "NC_59") (pintype "passive"))
      (node (ref "R237") (pin "1") (pinfunction "1_1") (pintype "passive"))
    )
    (net (code "72") (name "Net-(IC38A-+FB1)") (class "Default")
      (node (ref "IC38") (pin "2") (pinfunction "+FB1_2") (pintype "output"))
      (node (ref "R213") (pin "1") (pinfunction "1_1") (pintype "passive"))
    )
    (net (code "73") (name "Net-(IC38A-+IN1)") (class "Default")
      (node (ref "IC38") (pin "24") (pinfunction "+IN1_24") (pintype "input"))
      (node (ref "R209") (pin "2") (pinfunction "2_2") (pintype "passive"))
      (node (ref "R214") (pin "1") (pinfunction "1_1") (pintype "passive"))
    )
    (net (code "74") (name "Net-(IC38A--FB1)") (class "Default")
      (node (ref "IC38") (pin "23") (pinfunction "-FB1_23") (pintype "output"))
      (node (ref "R209") (pin "1") (pinfunction "1_1") (pintype "passive"))
    )
    (net (code "75") (name "Net-(IC38A--IN1)") (class "Default")
      (node (ref "IC38") (pin "1") (pinfunction "-IN1_1") (pintype "input"))
      (node (ref "R210") (pin "1") (pinfunction "1_1") (pintype "passive"))
      (node (ref "R213") (pin "2") (pinfunction "2_2") (pintype "passive"))
    )
    (net (code "76") (name "Net-(IC38B-+FB2)") (class "Default")
      (node (ref "IC38") (pin "8") (pinfunction "+FB2_8") (pintype "output"))
      (node (ref "R228") (pin "1") (pinfunction "1_1") (pintype "passive"))
    )
    (net (code "77") (name "Net-(IC38B-+IN2)") (class "Default")
      (node (ref "IC38") (pin "6") (pinfunction "+IN2_6") (pintype "input"))
      (node (ref "R224") (pin "2") (pinfunction "2_2") (pintype "passive"))
      (node (ref "R229") (pin "1") (pinfunction "1_1") (pintype "passive"))
    )
    (net (code "78") (name "Net-(IC38B--FB2)") (class "Default")
      (node (ref "IC38") (pin "5") (pinfunction "-FB2_5") (pintype "output"))
      (node (ref "R224") (pin "1") (pinfunction "1_1") (pintype "passive"))
    )
    (net (code "79") (name "Net-(IC38B--IN2)") (class "Default")
      (node (ref "IC38") (pin "7") (pinfunction "-IN2_7") (pintype "input"))
      (node (ref "R225") (pin "1") (pinfunction "1_1") (pintype "passive"))
      (node (ref "R228") (pin "2") (pinfunction "2_2") (pintype "passive"))
    )
    (net (code "80") (name "VCC1P8") (class "Default")
      (node (ref "FR81") (pin "1") (pinfunction "1_1") (pintype "passive"))
      (node (ref "FR82") (pin "1") (pinfunction "1_1") (pintype "passive"))
    )
    (net (code "81") (name "VCC1P8A_ADC") (class "Default")
      (node (ref "C664") (pin "2") (pinfunction "2_2") (pintype "passive"))
      (node (ref "C665") (pin "2") (pinfunction "2_2") (pintype "passive"))
      (node (ref "C666") (pin "2") (pinfunction "2_2") (pintype "passive"))
      (node (ref "C667") (pin "2") (pinfunction "2_2") (pintype "passive"))
      (node (ref "C668") (pin "2") (pinfunction "2_2") (pintype "passive"))
      (node (ref "C669") (pin "2") (pinfunction "2_2") (pintype "passive"))
      (node (ref "C670") (pin "2") (pinfunction "2_2") (pintype "passive"))
      (node (ref "C671") (pin "2") (pinfunction "2_2") (pintype "passive"))
      (node (ref "C672") (pin "1") (pinfunction "1_1") (pintype "passive"))
      (node (ref "FR82") (pin "2") (pinfunction "2_2") (pintype "passive"))
      (node (ref "IC37") (pin "16") (pinfunction "AVDD_16") (pintype "power_in"))
      (node (ref "IC37") (pin "22") (pinfunction "AVDD_22") (pintype "power_in"))
      (node (ref "IC37") (pin "33") (pinfunction "AVDD_33") (pintype "power_in"))
      (node (ref "IC37") (pin "34") (pinfunction "AVDD_34") (pintype "power_in"))
      (node (ref "R234") (pin "1") (pinfunction "1_1") (pintype "passive"))
    )
    (net (code "82") (name "VCC1P8D_ADC") (class "Default")
      (node (ref "C658") (pin "2") (pinfunction "2_2") (pintype "passive"))
      (node (ref "C659") (pin "2") (pinfunction "2_2") (pintype "passive"))
      (node (ref "C660") (pin "2") (pinfunction "2_2") (pintype "passive"))
      (node (ref "C661") (pin "2") (pinfunction "2_2") (pintype "passive"))
      (node (ref "C662") (pin "2") (pinfunction "2_2") (pintype "passive"))
      (node (ref "C663") (pin "1") (pinfunction "1_1") (pintype "passive"))
      (node (ref "FR81") (pin "2") (pinfunction "2_2") (pintype "passive"))
      (node (ref "IC37") (pin "1") (pinfunction "DRVDD_1") (pintype "power_in"))
      (node (ref "IC37") (pin "48") (pinfunction "DRVDD_48") (pintype "power_in"))
      (node (ref "R219") (pin "2") (pinfunction "2_2") (pintype "passive"))
      (node (ref "R221") (pin "2") (pinfunction "2_2") (pintype "passive"))
      (node (ref "R235") (pin "2") (pinfunction "2_2") (pintype "passive"))
      (node (ref "R238") (pin "2") (pinfunction "2_2") (pintype "passive"))
      (node (ref "R240") (pin "2") (pinfunction "2_2") (pintype "passive"))
      (node (ref "R242") (pin "2") (pinfunction "2_2") (pintype "passive"))
    )
    (net (code "83") (name "VCC3P3") (class "Default")
      (node (ref "R220") (pin "2") (pinfunction "2_2") (pintype "passive"))
    )
    (net (code "84") (name "VCC3P3_CLK") (class "Default")
      (node (ref "C673") (pin "1") (pinfunction "1_1") (pintype "passive"))
      (node (ref "C674") (pin "2") (pinfunction "2_2") (pintype "passive"))
      (node (ref "IC39") (pin "1") (pinfunction "VCC_1") (pintype "passive"))
    )
    (net (code "85") (name "VCC5P0") (class "Default")
      (node (ref "R223") (pin "2") (pinfunction "2_2") (pintype "passive"))
    )
    (net (code "86") (name "VCC_ADCDRV") (class "Default")
      (node (ref "C644") (pin "2") (pinfunction "2_2") (pintype "passive"))
      (node (ref "C645") (pin "2") (pinfunction "2_2") (pintype "passive"))
      (node (ref "C646") (pin "2") (pinfunction "2_2") (pintype "passive"))
      (node (ref "C647") (pin "1") (pinfunction "1_1") (pintype "passive"))
      (node (ref "C648") (pin "2") (pinfunction "2_2") (pintype "passive"))
      (node (ref "C654") (pin "2") (pinfunction "2_2") (pintype "passive"))
      (node (ref "C655") (pin "2") (pinfunction "2_2") (pintype "passive"))
      (node (ref "C656") (pin "2") (pinfunction "2_2") (pintype "passive"))
      (node (ref "C657") (pin "1") (pinfunction "1_1") (pintype "passive"))
      (node (ref "FR80") (pin "2") (pinfunction "2_2") (pintype "passive"))
      (node (ref "IC38") (pin "10") (pinfunction "+VS2_10") (pintype "power_in"))
      (node (ref "IC38") (pin "3") (pinfunction "+VS1_3") (pintype "power_in"))
      (node (ref "IC38") (pin "4") (pinfunction "+VS1_4") (pintype "power_in"))
      (node (ref "IC38") (pin "9") (pinfunction "+VS2_9") (pintype "power_in"))
      (node (ref "R222") (pin "2") (pinfunction "2_2") (pintype "passive"))
    )
    (net (code "87") (name "unconnected-(FL5-Pad1)") (class "Default")
      (node (ref "FL5") (pin "1") (pintype "passive+no_connect"))
    )
  )
)
